# USB_SPI_Flash.net
KiCad netlist of a schematic drawn in Altium Designer
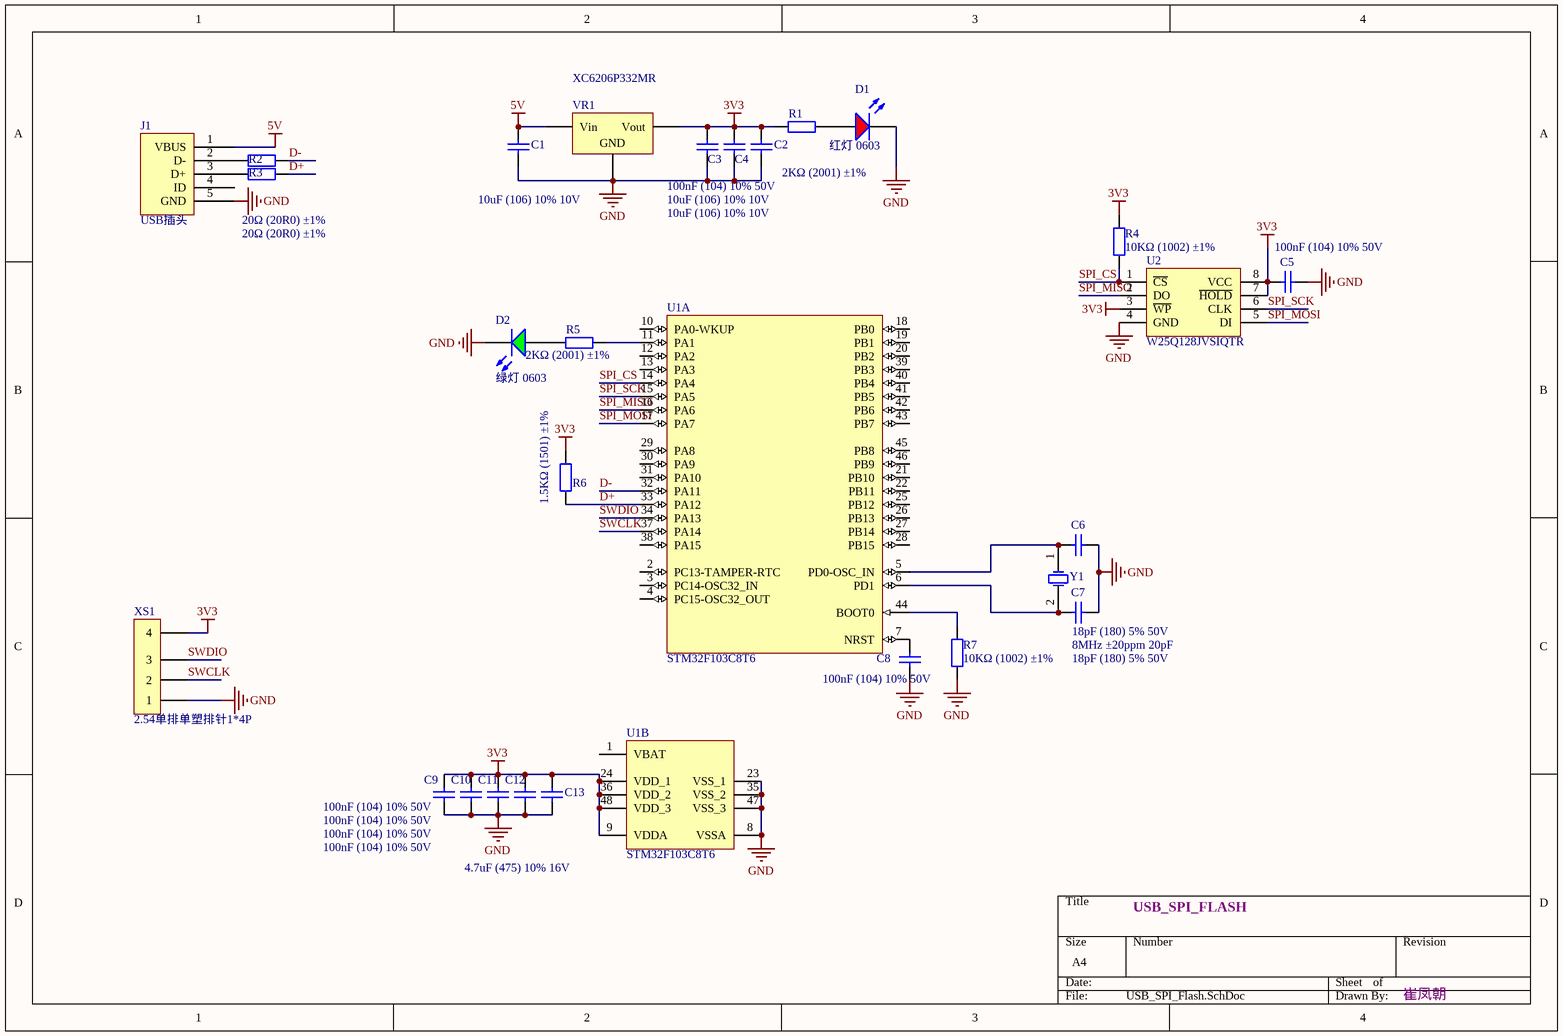
[diagram p0: USB_SPI_Flash.SchDoc]

(export (version "E")
  (design (tool "Eeschema 10.0.6"))
  (components
    (comp (ref "C1")
      (value "10uF (106) 10% 10V")
      (footprint "0603_C")
      (description "贴片电容")
      (libsource (lib "Cap") (part "0603 10uF (106) 10% 10V"))
    )
    (comp (ref "C2")
      (value "100nF (104) 10% 50V")
      (footprint "0603_C")
      (description "贴片电容")
      (libsource (lib "Cap") (part "0603 100nF (104) 10% 50V"))
    )
    (comp (ref "C3")
      (value "10uF (106) 10% 10V")
      (footprint "0603_C")
      (description "贴片电容")
      (libsource (lib "Cap") (part "0603 10uF (106) 10% 10V"))
    )
    (comp (ref "C4")
      (value "10uF (106) 10% 10V")
      (footprint "0603_C")
      (description "贴片电容")
      (libsource (lib "Cap") (part "0603 10uF (106) 10% 10V"))
    )
    (comp (ref "C5")
      (value "100nF (104) 10% 50V")
      (footprint "0603_C")
      (description "贴片电容")
      (libsource (lib "Cap") (part "0603 100nF (104) 10% 50V"))
    )
    (comp (ref "C6")
      (value "18pF (180) 5% 50V")
      (footprint "0603_C")
      (description "贴片电容")
      (libsource (lib "Cap") (part "0603 18pF (180) 5% 50V"))
    )
    (comp (ref "C7")
      (value "18pF (180) 5% 50V")
      (footprint "0603_C")
      (description "贴片电容")
      (libsource (lib "Cap") (part "0603 18pF (180) 5% 50V"))
    )
    (comp (ref "C8")
      (value "100nF (104) 10% 50V")
      (footprint "0603_C")
      (description "贴片电容")
      (libsource (lib "Cap") (part "0603 100nF (104) 10% 50V"))
    )
    (comp (ref "C9")
      (value "100nF (104) 10% 50V")
      (footprint "0603_C")
      (description "贴片电容")
      (libsource (lib "Cap") (part "0603 100nF (104) 10% 50V"))
    )
    (comp (ref "C10")
      (value "100nF (104) 10% 50V")
      (footprint "0603_C")
      (description "贴片电容")
      (libsource (lib "Cap") (part "0603 100nF (104) 10% 50V"))
    )
    (comp (ref "C11")
      (value "100nF (104) 10% 50V")
      (footprint "0603_C")
      (description "贴片电容")
      (libsource (lib "Cap") (part "0603 100nF (104) 10% 50V"))
    )
    (comp (ref "C12")
      (value "100nF (104) 10% 50V")
      (footprint "0603_C")
      (description "贴片电容")
      (libsource (lib "Cap") (part "0603 100nF (104) 10% 50V"))
    )
    (comp (ref "C13")
      (value "4.7uF (475) 10% 16V")
      (footprint "0603_C")
      (description "贴片电容")
      (libsource (lib "Cap") (part "0603 4.7uF (475) 10% 16V"))
    )
    (comp (ref "D1")
      (value "红灯 0603")
      (footprint "0603_LED_S1")
      (description "发光二极管")
      (libsource (lib "LED") (part "0603 红灯"))
    )
    (comp (ref "D2")
      (value "绿灯 0603")
      (footprint "0603_LED_S1")
      (description "发光二极管")
      (libsource (lib "LED") (part "0603 绿灯"))
    )
    (comp (ref "J1")
      (value "USB插头")
      (footprint "MICRO-USB-SMD_5P-P0.65-H-F_MICRO5.9MMUSB")
      (libsource (lib "Sdkd_schlib") (part "USB-SMD-5.9MM"))
    )
    (comp (ref "R1")
      (value "2KΩ (2001) ±1%")
      (footprint "0603_R")
      (description "贴片电阻")
      (libsource (lib "RES") (part "0603 2KΩ (2001) 1%"))
    )
    (comp (ref "R2")
      (value "20Ω (20R0) ±1%")
      (footprint "0603_R")
      (description "贴片电阻")
      (libsource (lib "RES") (part "0603 20Ω (20R0) 1%"))
    )
    (comp (ref "R3")
      (value "20Ω (20R0) ±1%")
      (footprint "0603_R")
      (description "贴片电阻")
      (libsource (lib "RES") (part "0603 20Ω (20R0) 1%"))
    )
    (comp (ref "R4")
      (value "10KΩ (1002) ±1%")
      (footprint "0603_R")
      (description "贴片电阻")
      (libsource (lib "RES") (part "0603 10KΩ (1002) 1%"))
    )
    (comp (ref "R5")
      (value "2KΩ (2001) ±1%")
      (footprint "0603_R")
      (description "贴片电阻")
      (libsource (lib "RES") (part "0603 2KΩ (2001) 1%"))
    )
    (comp (ref "R6")
      (value "1.5KΩ (1501) ±1%")
      (footprint "0603_R")
      (description "贴片电阻")
      (libsource (lib "RES") (part "0603 1.5KΩ (1501) 1%"))
    )
    (comp (ref "R7")
      (value "10KΩ (1002) ±1%")
      (footprint "0603_R")
      (description "贴片电阻")
      (libsource (lib "RES") (part "0603 10KΩ (1002) 1%"))
    )
    (comp (ref "U1")
      (value "STM32F103C8T6")
      (footprint "LQFP-48_7x7x05P")
      (description "ARM")
      (libsource (lib "MCU") (part "STM32F103C8T6"))
    )
    (comp (ref "U2")
      (value "W25Q128JVSIQTR")
      (footprint "SOIC-8_208mil")
      (description "Flash ROM")
      (libsource (lib "IC") (part "W25Q128JVSIQTR_[C97521]"))
    )
    (comp (ref "VR1")
      (value "XC6206P332MR")
      (footprint "SOT-23-3L")
      (description "低压差线性稳压(LDO)")
      (libsource (lib "LDO") (part "SOT-23 XC6206P332MR"))
    )
    (comp (ref "XS1")
      (value "2.54单排单塑排针1*4P")
      (footprint "PIN4")
      (libsource (lib "Sdkd_schlib") (part "2.54单排单塑排针1*4P"))
    )
    (comp (ref "Y1")
      (value "8MHz ±20ppm 20pF")
      (footprint "SMD-5032_2P")
      (description "贴片晶振")
      (libsource (lib "CrystalOscillator") (part "SMD-5032_2P 8MHz 20ppm 20pF"))
    )
  )
  (nets
    (net (code "1") (name "/D+") (class "Default")
      (node (ref "R3") (pin "2") (pinfunction "2_2") (pintype "passive"))
      (node (ref "R6") (pin "1") (pinfunction "1_1") (pintype "passive"))
      (node (ref "U1") (pin "33") (pinfunction "PA12_33") (pintype "bidirectional"))
    )
    (net (code "2") (name "/D-") (class "Default")
      (node (ref "R2") (pin "2") (pinfunction "2_2") (pintype "passive"))
      (node (ref "U1") (pin "32") (pinfunction "PA11_32") (pintype "bidirectional"))
    )
    (net (code "3") (name "/SPI_CS") (class "Default")
      (node (ref "R4") (pin "1") (pinfunction "1_1") (pintype "passive"))
      (node (ref "U1") (pin "14") (pinfunction "PA4_14") (pintype "bidirectional"))
      (node (ref "U2") (pin "1") (pinfunction "~{CS}_1") (pintype "passive"))
    )
    (net (code "4") (name "/SPI_MISO") (class "Default")
      (node (ref "U1") (pin "16") (pinfunction "PA6_16") (pintype "bidirectional"))
      (node (ref "U2") (pin "2") (pinfunction "DO_2") (pintype "passive"))
    )
    (net (code "5") (name "/SPI_MOSI") (class "Default")
      (node (ref "U1") (pin "17") (pinfunction "PA7_17") (pintype "bidirectional"))
      (node (ref "U2") (pin "5") (pinfunction "DI_5") (pintype "passive"))
    )
    (net (code "6") (name "/SPI_SCK") (class "Default")
      (node (ref "U1") (pin "15") (pinfunction "PA5_15") (pintype "bidirectional"))
      (node (ref "U2") (pin "6") (pinfunction "CLK_6") (pintype "passive"))
    )
    (net (code "7") (name "/SWCLK") (class "Default")
      (node (ref "U1") (pin "37") (pinfunction "PA14_37") (pintype "bidirectional"))
      (node (ref "XS1") (pin "2") (pinfunction "2_2") (pintype "passive"))
    )
    (net (code "8") (name "/SWDIO") (class "Default")
      (node (ref "U1") (pin "34") (pinfunction "PA13_34") (pintype "bidirectional"))
      (node (ref "XS1") (pin "3") (pinfunction "3_3") (pintype "passive"))
    )
    (net (code "11") (name "3V3") (class "Default")
      (node (ref "C10") (pin "2") (pinfunction "2_2") (pintype "passive"))
      (node (ref "C11") (pin "2") (pinfunction "2_2") (pintype "passive"))
      (node (ref "C12") (pin "2") (pinfunction "2_2") (pintype "passive"))
      (node (ref "C13") (pin "2") (pinfunction "2_2") (pintype "passive"))
      (node (ref "C2") (pin "2") (pinfunction "2_2") (pintype "passive"))
      (node (ref "C3") (pin "2") (pinfunction "2_2") (pintype "passive"))
      (node (ref "C4") (pin "2") (pinfunction "2_2") (pintype "passive"))
      (node (ref "C5") (pin "2") (pinfunction "2_2") (pintype "passive"))
      (node (ref "C9") (pin "2") (pinfunction "2_2") (pintype "passive"))
      (node (ref "R1") (pin "2") (pinfunction "2_2") (pintype "passive"))
      (node (ref "R4") (pin "2") (pinfunction "2_2") (pintype "passive"))
      (node (ref "R6") (pin "2") (pinfunction "2_2") (pintype "passive"))
      (node (ref "U1") (pin "24") (pinfunction "VDD_1_24") (pintype "power_in"))
      (node (ref "U1") (pin "36") (pinfunction "VDD_2_36") (pintype "power_in"))
      (node (ref "U1") (pin "48") (pinfunction "VDD_3_48") (pintype "power_in"))
      (node (ref "U1") (pin "9") (pinfunction "VDDA_9") (pintype "power_in"))
      (node (ref "U2") (pin "3") (pinfunction "~{WP}_3") (pintype "passive"))
      (node (ref "U2") (pin "7") (pinfunction "~{HOLD}_7") (pintype "passive"))
      (node (ref "U2") (pin "8") (pinfunction "VCC_8") (pintype "passive"))
      (node (ref "VR1") (pin "2") (pinfunction "Vout_2") (pintype "passive"))
      (node (ref "XS1") (pin "4") (pinfunction "4_4") (pintype "passive"))
    )
    (net (code "12") (name "5V") (class "Default")
      (node (ref "C1") (pin "2") (pinfunction "2_2") (pintype "passive"))
      (node (ref "J1") (pin "1") (pinfunction "VBUS_1") (pintype "passive"))
      (node (ref "VR1") (pin "3") (pinfunction "Vin_3") (pintype "passive"))
    )
    (net (code "13") (name "GND") (class "Default")
      (node (ref "C1") (pin "1") (pinfunction "1_1") (pintype "passive"))
      (node (ref "C10") (pin "1") (pinfunction "1_1") (pintype "passive"))
      (node (ref "C11") (pin "1") (pinfunction "1_1") (pintype "passive"))
      (node (ref "C12") (pin "1") (pinfunction "1_1") (pintype "passive"))
      (node (ref "C13") (pin "1") (pinfunction "1_1") (pintype "passive"))
      (node (ref "C2") (pin "1") (pinfunction "1_1") (pintype "passive"))
      (node (ref "C3") (pin "1") (pinfunction "1_1") (pintype "passive"))
      (node (ref "C4") (pin "1") (pinfunction "1_1") (pintype "passive"))
      (node (ref "C5") (pin "1") (pinfunction "1_1") (pintype "passive"))
      (node (ref "C6") (pin "1") (pinfunction "1_1") (pintype "passive"))
      (node (ref "C7") (pin "1") (pinfunction "1_1") (pintype "passive"))
      (node (ref "C8") (pin "1") (pinfunction "1_1") (pintype "passive"))
      (node (ref "C9") (pin "1") (pinfunction "1_1") (pintype "passive"))
      (node (ref "D1") (pin "K") (pinfunction "K_K") (pintype "passive"))
      (node (ref "D2") (pin "K") (pinfunction "K_K") (pintype "passive"))
      (node (ref "J1") (pin "5") (pinfunction "GND_5") (pintype "passive"))
      (node (ref "R7") (pin "1") (pinfunction "1_1") (pintype "passive"))
      (node (ref "U1") (pin "23") (pinfunction "VSS_1_23") (pintype "power_in"))
      (node (ref "U1") (pin "35") (pinfunction "VSS_2_35") (pintype "power_in"))
      (node (ref "U1") (pin "47") (pinfunction "VSS_3_47") (pintype "power_in"))
      (node (ref "U1") (pin "8") (pinfunction "VSSA_8") (pintype "power_in"))
      (node (ref "U2") (pin "4") (pinfunction "GND_4") (pintype "passive"))
      (node (ref "VR1") (pin "1") (pinfunction "GND_1") (pintype "passive"))
      (node (ref "XS1") (pin "1") (pinfunction "1_1") (pintype "passive"))
    )
    (net (code "14") (name "Net-(D1-PadA)") (class "Default")
      (node (ref "D1") (pin "A") (pinfunction "A_A") (pintype "passive"))
      (node (ref "R1") (pin "1") (pinfunction "1_1") (pintype "passive"))
    )
    (net (code "15") (name "Net-(D2-PadA)") (class "Default")
      (node (ref "D2") (pin "A") (pinfunction "A_A") (pintype "passive"))
      (node (ref "R5") (pin "2") (pinfunction "2_2") (pintype "passive"))
    )
    (net (code "16") (name "Net-(J1-D+)") (class "Default")
      (node (ref "J1") (pin "3") (pinfunction "D+_3") (pintype "passive"))
      (node (ref "R3") (pin "1") (pinfunction "1_1") (pintype "passive"))
    )
    (net (code "17") (name "Net-(J1-D-)") (class "Default")
      (node (ref "J1") (pin "2") (pinfunction "D-_2") (pintype "passive"))
      (node (ref "R2") (pin "1") (pinfunction "1_1") (pintype "passive"))
    )
    (net (code "18") (name "Net-(U1A-BOOT0)") (class "Default")
      (node (ref "R7") (pin "2") (pinfunction "2_2") (pintype "passive"))
      (node (ref "U1") (pin "44") (pinfunction "BOOT0_44") (pintype "input"))
    )
    (net (code "19") (name "Net-(U1A-NRST)") (class "Default")
      (node (ref "C8") (pin "2") (pinfunction "2_2") (pintype "passive"))
      (node (ref "U1") (pin "7") (pinfunction "NRST_7") (pintype "bidirectional"))
    )
    (net (code "20") (name "Net-(U1A-PA1)") (class "Default")
      (node (ref "R5") (pin "1") (pinfunction "1_1") (pintype "passive"))
      (node (ref "U1") (pin "11") (pinfunction "PA1_11") (pintype "bidirectional"))
    )
    (net (code "21") (name "Net-(U1A-PD0-OSC_IN)") (class "Default")
      (node (ref "C6") (pin "2") (pinfunction "2_2") (pintype "passive"))
      (node (ref "U1") (pin "5") (pinfunction "PD0-OSC_IN_5") (pintype "bidirectional"))
      (node (ref "Y1") (pin "1") (pinfunction "OSC1_1") (pintype "passive"))
    )
    (net (code "22") (name "Net-(U1A-PD1)") (class "Default")
      (node (ref "C7") (pin "2") (pinfunction "2_2") (pintype "passive"))
      (node (ref "U1") (pin "6") (pinfunction "PD1_6") (pintype "bidirectional"))
      (node (ref "Y1") (pin "2") (pinfunction "OSC2_2") (pintype "passive"))
    )
    (net (code "23") (name "unconnected-(J1-ID-Pad4)") (class "Default")
      (node (ref "J1") (pin "4") (pinfunction "ID_4") (pintype "passive"))
    )
    (net (code "24") (name "unconnected-(U1A-PA0-WKUP-Pad10)") (class "Default")
      (node (ref "U1") (pin "10") (pinfunction "PA0-WKUP_10") (pintype "bidirectional"))
    )
    (net (code "25") (name "unconnected-(U1A-PA2-Pad12)") (class "Default")
      (node (ref "U1") (pin "12") (pinfunction "PA2_12") (pintype "bidirectional"))
    )
    (net (code "26") (name "unconnected-(U1A-PA3-Pad13)") (class "Default")
      (node (ref "U1") (pin "13") (pinfunction "PA3_13") (pintype "bidirectional"))
    )
    (net (code "27") (name "unconnected-(U1A-PA8-Pad29)") (class "Default")
      (node (ref "U1") (pin "29") (pinfunction "PA8_29") (pintype "bidirectional"))
    )
    (net (code "28") (name "unconnected-(U1A-PA9-Pad30)") (class "Default")
      (node (ref "U1") (pin "30") (pinfunction "PA9_30") (pintype "bidirectional"))
    )
    (net (code "29") (name "unconnected-(U1A-PA10-Pad31)") (class "Default")
      (node (ref "U1") (pin "31") (pinfunction "PA10_31") (pintype "bidirectional"))
    )
    (net (code "30") (name "unconnected-(U1A-PA15-Pad38)") (class "Default")
      (node (ref "U1") (pin "38") (pinfunction "PA15_38") (pintype "bidirectional"))
    )
    (net (code "31") (name "unconnected-(U1A-PB0-Pad18)") (class "Default")
      (node (ref "U1") (pin "18") (pinfunction "PB0_18") (pintype "bidirectional"))
    )
    (net (code "32") (name "unconnected-(U1A-PB1-Pad19)") (class "Default")
      (node (ref "U1") (pin "19") (pinfunction "PB1_19") (pintype "bidirectional"))
    )
    (net (code "33") (name "unconnected-(U1A-PB2-Pad20)") (class "Default")
      (node (ref "U1") (pin "20") (pinfunction "PB2_20") (pintype "bidirectional"))
    )
    (net (code "34") (name "unconnected-(U1A-PB3-Pad39)") (class "Default")
      (node (ref "U1") (pin "39") (pinfunction "PB3_39") (pintype "bidirectional"))
    )
    (net (code "35") (name "unconnected-(U1A-PB4-Pad40)") (class "Default")
      (node (ref "U1") (pin "40") (pinfunction "PB4_40") (pintype "bidirectional"))
    )
    (net (code "36") (name "unconnected-(U1A-PB5-Pad41)") (class "Default")
      (node (ref "U1") (pin "41") (pinfunction "PB5_41") (pintype "bidirectional"))
    )
    (net (code "37") (name "unconnected-(U1A-PB6-Pad42)") (class "Default")
      (node (ref "U1") (pin "42") (pinfunction "PB6_42") (pintype "bidirectional"))
    )
    (net (code "38") (name "unconnected-(U1A-PB7-Pad43)") (class "Default")
      (node (ref "U1") (pin "43") (pinfunction "PB7_43") (pintype "bidirectional"))
    )
    (net (code "39") (name "unconnected-(U1A-PB8-Pad45)") (class "Default")
      (node (ref "U1") (pin "45") (pinfunction "PB8_45") (pintype "bidirectional"))
    )
    (net (code "40") (name "unconnected-(U1A-PB9-Pad46)") (class "Default")
      (node (ref "U1") (pin "46") (pinfunction "PB9_46") (pintype "bidirectional"))
    )
    (net (code "41") (name "unconnected-(U1A-PB10-Pad21)") (class "Default")
      (node (ref "U1") (pin "21") (pinfunction "PB10_21") (pintype "bidirectional"))
    )
    (net (code "42") (name "unconnected-(U1A-PB11-Pad22)") (class "Default")
      (node (ref "U1") (pin "22") (pinfunction "PB11_22") (pintype "bidirectional"))
    )
    (net (code "43") (name "unconnected-(U1A-PB12-Pad25)") (class "Default")
      (node (ref "U1") (pin "25") (pinfunction "PB12_25") (pintype "bidirectional"))
    )
    (net (code "44") (name "unconnected-(U1A-PB13-Pad26)") (class "Default")
      (node (ref "U1") (pin "26") (pinfunction "PB13_26") (pintype "bidirectional"))
    )
    (net (code "45") (name "unconnected-(U1A-PB14-Pad27)") (class "Default")
      (node (ref "U1") (pin "27") (pinfunction "PB14_27") (pintype "bidirectional"))
    )
    (net (code "46") (name "unconnected-(U1A-PB15-Pad28)") (class "Default")
      (node (ref "U1") (pin "28") (pinfunction "PB15_28") (pintype "bidirectional"))
    )
    (net (code "47") (name "unconnected-(U1A-PC13-TAMPER-RTC-Pad2)") (class "Default")
      (node (ref "U1") (pin "2") (pinfunction "PC13-TAMPER-RTC_2") (pintype "bidirectional"))
    )
    (net (code "48") (name "unconnected-(U1A-PC14-OSC32_IN-Pad3)") (class "Default")
      (node (ref "U1") (pin "3") (pinfunction "PC14-OSC32_IN_3") (pintype "bidirectional"))
    )
    (net (code "49") (name "unconnected-(U1A-PC15-OSC32_OUT-Pad4)") (class "Default")
      (node (ref "U1") (pin "4") (pinfunction "PC15-OSC32_OUT_4") (pintype "bidirectional"))
    )
    (net (code "50") (name "unconnected-(U1B-VBAT-Pad1)") (class "Default")
      (node (ref "U1") (pin "1") (pinfunction "VBAT_1") (pintype "power_in"))
    )
  )
)
